# 2022-07-29_LVMi_Pressure_Sensor_-_1624.net
KiCad netlist of a schematic drawn in EAGLE
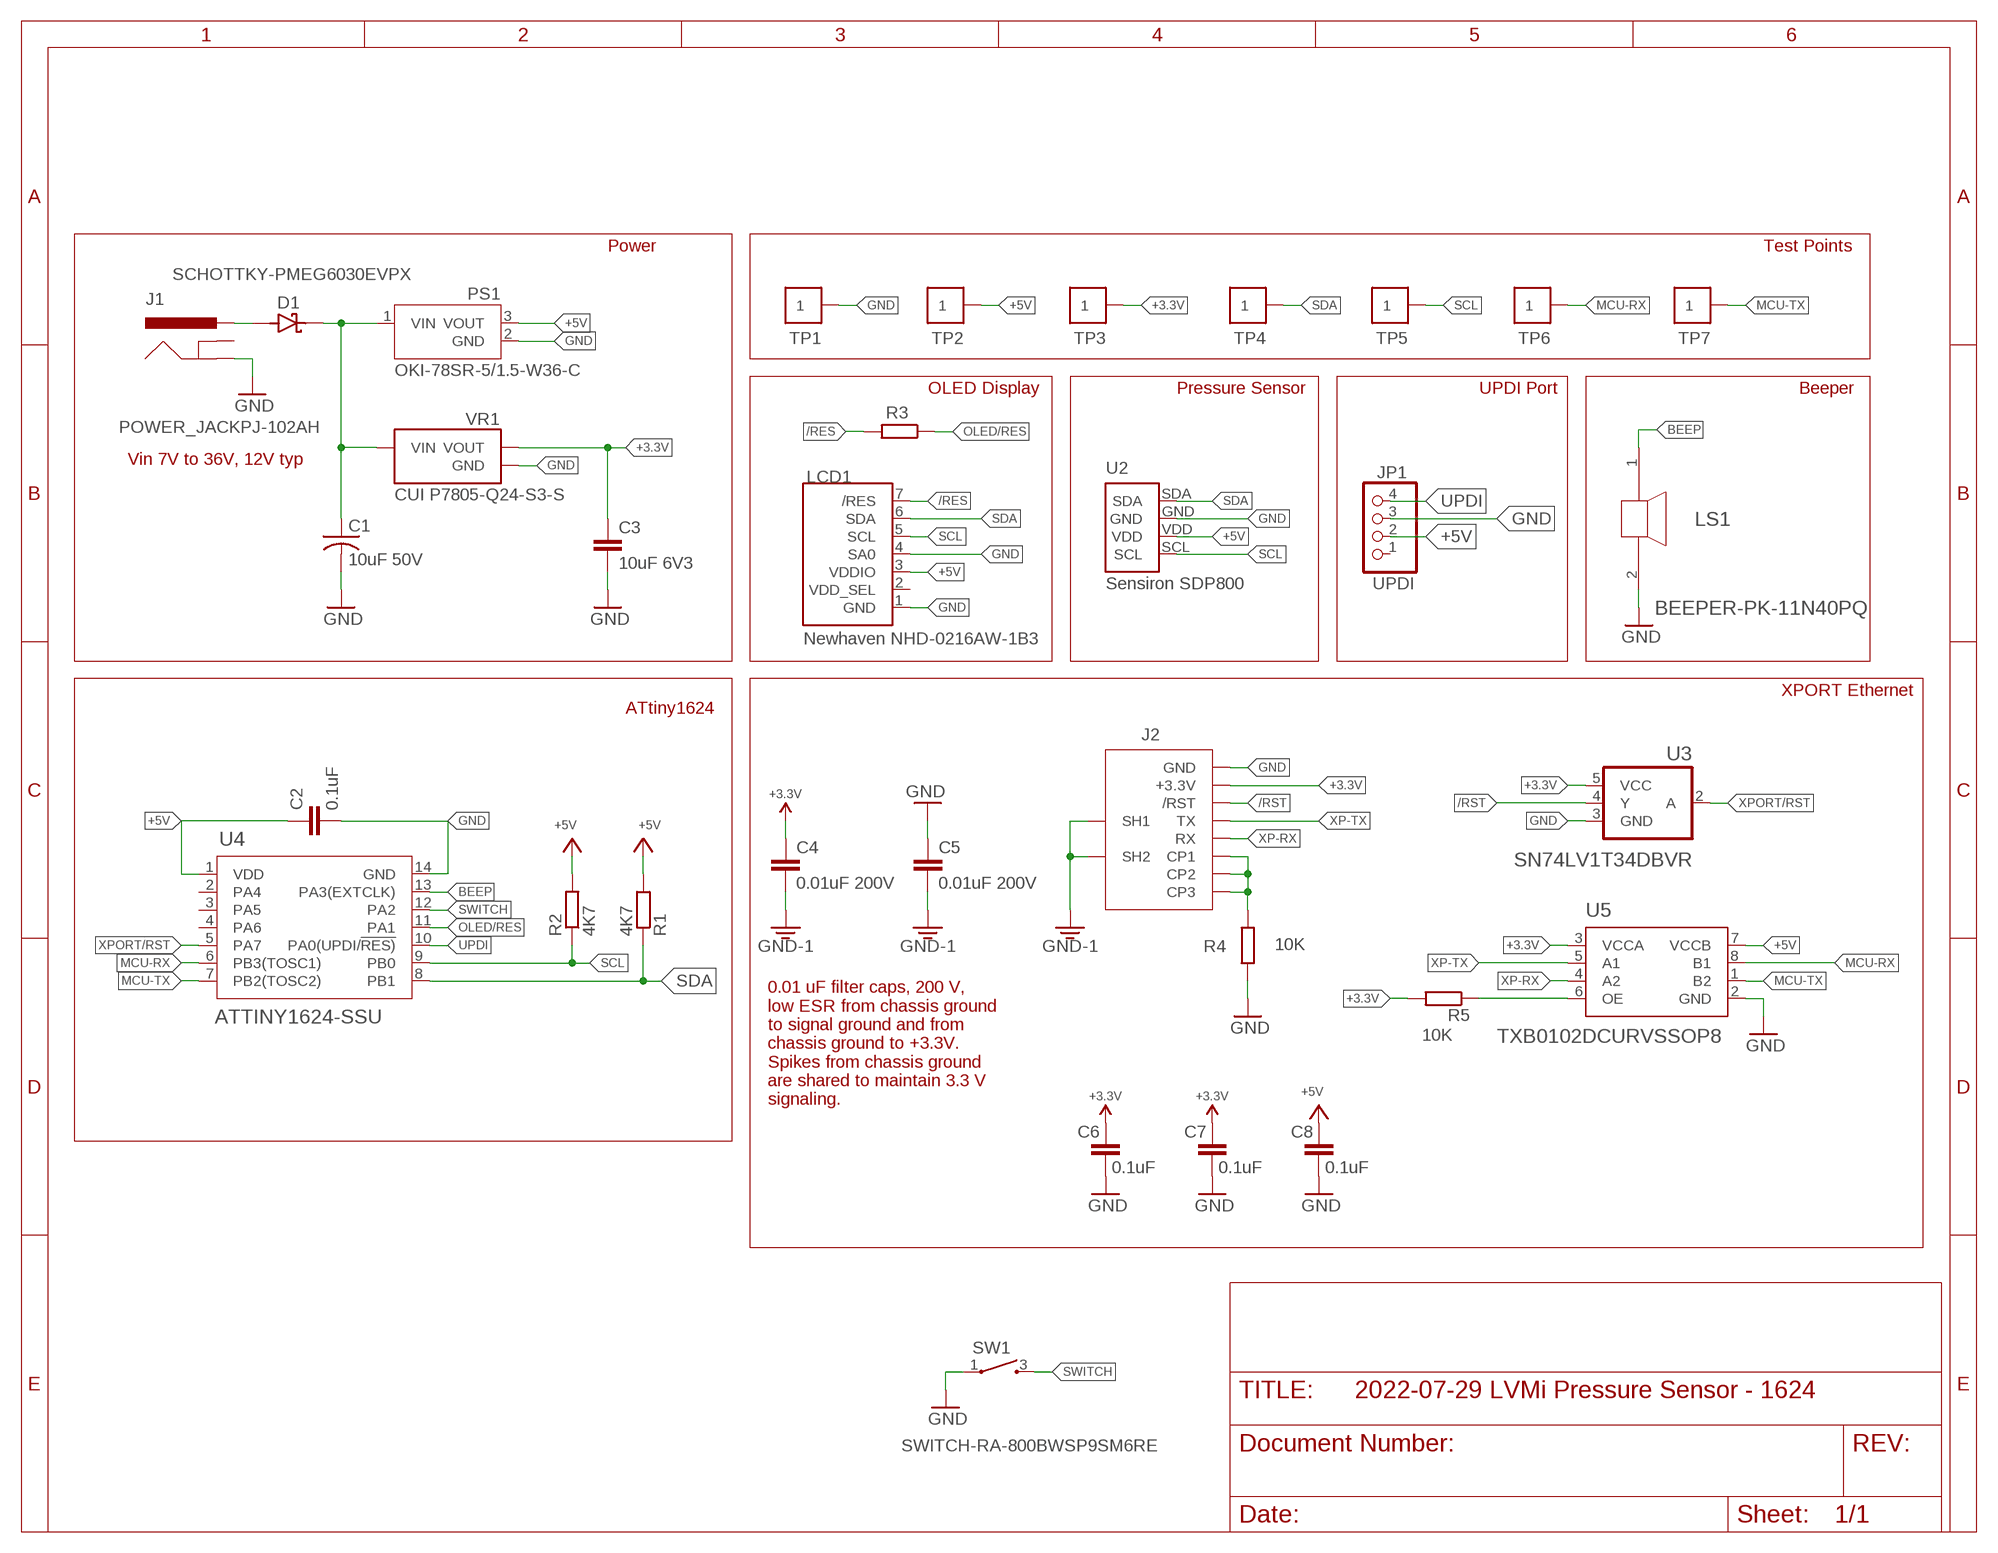
[diagram p0: schematic, sheet 1]

(export (version "E")
  (design (tool "Eeschema 10.0.6"))
  (components
    (comp (ref "C1")
      (value "10uF 50V")
      (footprint "eagle-import:C1210")
      (libsource (lib "eagle-import") (part "C-USC1210"))
    )
    (comp (ref "C2")
      (value "0.1uF")
      (footprint "eagle-import:C0805")
      (libsource (lib "eagle-import") (part "C-EUC0805"))
    )
    (comp (ref "C3")
      (value "10uF 6V3")
      (footprint "eagle-import:C0805")
      (libsource (lib "eagle-import") (part "C-EUC0805"))
    )
    (comp (ref "C4")
      (value "0.01uF 200V")
      (footprint "eagle-import:C0805")
      (libsource (lib "eagle-import") (part "C-EUC0805"))
    )
    (comp (ref "C5")
      (value "0.01uF 200V")
      (footprint "eagle-import:C0805")
      (libsource (lib "eagle-import") (part "C-EUC0805"))
    )
    (comp (ref "C6")
      (value "0.1uF")
      (footprint "eagle-import:C0805")
      (libsource (lib "eagle-import") (part "C-EUC0805"))
    )
    (comp (ref "C7")
      (value "0.1uF")
      (footprint "eagle-import:C0805")
      (libsource (lib "eagle-import") (part "C-EUC0805"))
    )
    (comp (ref "C8")
      (value "0.1uF")
      (footprint "eagle-import:C0805")
      (libsource (lib "eagle-import") (part "C-EUC0805"))
    )
    (comp (ref "D1")
      (value "SCHOTTKY-PMEG6030EVPX")
      (footprint "eagle-import:DIO_PMEG6030EVPX")
      (fields
        (field (name "DIGI-KEY_PART_NUMBER") "1727-1349-1-ND")
        (field (name "MF") "Nexperia USA")
        (field (name "MP") "PMEG6030EVPX")
      )
      (libsource (lib "eagle-import") (part "SCHOTTKY-PMEG6030EVPX"))
    )
    (comp (ref "J1")
      (value "POWER_JACKPJ-102AH")
      (footprint "eagle-import:PJ-102AH")
      (libsource (lib "eagle-import") (part "POWER_JACKPJ-102AH"))
    )
    (comp (ref "J2")
      (value "XPORTXPORT-2")
      (footprint "eagle-import:XPORT-2")
      (libsource (lib "eagle-import") (part "XPORTXPORT-2"))
    )
    (comp (ref "JP1")
      (value "UPDI")
      (footprint "eagle-import:1X04_90")
      (libsource (lib "eagle-import") (part "PINHD-1X4/90"))
    )
    (comp (ref "LCD1")
      (value "Newhaven NHD-0216AW-1B3")
      (footprint "eagle-import:LCD-NEWHAVEN-16X2")
      (libsource (lib "eagle-import") (part "LCD-NEWHAVEN-16X2"))
    )
    (comp (ref "LS1")
      (value "BEEPER-PK-11N40PQ")
      (footprint "eagle-import:PK-11N40PQ_MAL")
      (fields
        (field (name "MANUFACTURER_PART_NUMBER") "PK-11N40PQ")
        (field (name "COPYRIGHT") "Copyright (C) 2022 Ultra Librarian. All rights reserved.")
      )
      (libsource (lib "eagle-import") (part "BEEPER-PK-11N40PQ"))
    )
    (comp (ref "PS1")
      (value "OKI-78SR-5/1.5-W36-C")
      (footprint "eagle-import:CONV_OKI-78SR-5_1.5-W36-C")
      (fields
        (field (name "DIGI-KEY_PART_NUMBER") "811-2196-5-ND")
        (field (name "MF") "Murata Power Solutions Inc.")
      )
      (libsource (lib "eagle-import") (part "OKI-78SR-5/1.5-W36-C"))
    )
    (comp (ref "R1")
      (value "4K7")
      (footprint "eagle-import:R0805")
      (libsource (lib "eagle-import") (part "R-EU_R0805"))
    )
    (comp (ref "R2")
      (value "4K7")
      (footprint "eagle-import:R0805")
      (libsource (lib "eagle-import") (part "R-EU_R0805"))
    )
    (comp (ref "R3")
      (value "R-EU_R0805")
      (footprint "eagle-import:R0805")
      (libsource (lib "eagle-import") (part "R-EU_R0805"))
    )
    (comp (ref "R4")
      (value "10K")
      (footprint "eagle-import:R0805")
      (libsource (lib "eagle-import") (part "R-EU_R0805"))
    )
    (comp (ref "R5")
      (value "10K")
      (footprint "eagle-import:R0805")
      (libsource (lib "eagle-import") (part "R-EU_R0805"))
    )
    (comp (ref "SW1")
      (value "SWITCH-RA-800BWSP9SM6RE")
      (footprint "eagle-import:SWITCH-RA-800BWSP9SM6RE")
      (libsource (lib "eagle-import") (part "SWITCH-RA-800BWSP9SM6RE"))
    )
    (comp (ref "TP1")
      (value "GND")
      (footprint "eagle-import:TP5000-TESTPOINT-BLK")
      (libsource (lib "eagle-import") (part "TP5000-TESTPOINT-BLK"))
    )
    (comp (ref "TP2")
      (value "+5V")
      (footprint "eagle-import:TP5000-TESTPOINT-RED")
      (libsource (lib "eagle-import") (part "TP5000-TESTPOINT-RED"))
    )
    (comp (ref "TP3")
      (value "+3.3V")
      (footprint "eagle-import:TP5000-TESTPOINT-PUR")
      (libsource (lib "eagle-import") (part "TP5000-TESTPOINT-PUR"))
    )
    (comp (ref "TP4")
      (value "SDA")
      (footprint "eagle-import:TP5000-TESTPOINT-YEL")
      (libsource (lib "eagle-import") (part "TP5000-TESTPOINT-YEL"))
    )
    (comp (ref "TP5")
      (value "SCL")
      (footprint "eagle-import:TP5000-TESTPOINT-WHI")
      (libsource (lib "eagle-import") (part "TP5000-TESTPOINT-WHI"))
    )
    (comp (ref "TP6")
      (value "MCU-RX")
      (footprint "eagle-import:TP5000-TESTPOINT-WHI")
      (libsource (lib "eagle-import") (part "TP5000-TESTPOINT-WHI"))
    )
    (comp (ref "TP7")
      (value "MCU-TX")
      (footprint "eagle-import:TP5000-TESTPOINT-WHI")
      (libsource (lib "eagle-import") (part "TP5000-TESTPOINT-WHI"))
    )
    (comp (ref "U2")
      (value "Sensiron SDP800")
      (footprint "eagle-import:SDP800_PRESSURE_SENSOR")
      (libsource (lib "eagle-import") (part "SDP800_PRESSURE_SENSOR"))
    )
    (comp (ref "U3")
      (value "SN74LV1T34DBVR")
      (footprint "eagle-import:SOT95P280X145-5N")
      (fields (field (name "DIGI-KEY_PART_NUMBER") "296-37176-1-ND") (field (name "MF") "Texas Instruments"))
      (libsource (lib "eagle-import") (part "SN74LV1T34DBVR"))
    )
    (comp (ref "U4")
      (value "ATTINY1624-SSU")
      (footprint "eagle-import:SOIC150-14_MCH-M")
      (fields (field (name "COPYRIGHT") "Copyright (C) 2022 Ultra Librarian. All rights reserved."))
      (libsource (lib "eagle-import") (part "ATTINY1624-SSUSOIC150-14_MCH-M"))
    )
    (comp (ref "U5")
      (value "TXB0102DCURVSSOP8")
      (footprint "eagle-import:GHI-IC_VSSOP8(TI)")
      (libsource (lib "eagle-import") (part "TXB0102DCURVSSOP8"))
    )
    (comp (ref "VR1")
      (value "CUI P7805-Q24-S3-S")
      (footprint "eagle-import:CONV_P7805-Q24-S3-S")
      (fields (field (name "MF") "CUI") (field (name "MP") "P7805-Q12-S1R5-S"))
      (libsource (lib "eagle-import") (part "P7805-Q24-S3-S"))
    )
  )
  (nets
    (net (code "1") (name "+3.3V") (class "Default")
      (node (ref "C3") (pin "1") (pinfunction "1_1") (pintype "passive"))
      (node (ref "C4") (pin "1") (pinfunction "1_1") (pintype "passive"))
      (node (ref "C6") (pin "2") (pinfunction "2_2") (pintype "passive"))
      (node (ref "C7") (pin "2") (pinfunction "2_2") (pintype "passive"))
      (node (ref "J2") (pin "3.3V") (pinfunction "+3.3V_3.3V") (pintype "power_in"))
      (node (ref "R5") (pin "2") (pinfunction "2_2") (pintype "passive"))
      (node (ref "TP3") (pin "P$1") (pinfunction "1_P$1") (pintype "bidirectional"))
      (node (ref "U3") (pin "5") (pinfunction "VCC_5") (pintype "power_in"))
      (node (ref "U5") (pin "3") (pinfunction "VCCA_3") (pintype "power_in"))
      (node (ref "VR1") (pin "VOUT") (pinfunction "VOUT_VOUT") (pintype "power_in"))
    )
    (net (code "2") (name "+5V") (class "Default")
      (node (ref "C2") (pin "1") (pinfunction "1_1") (pintype "passive"))
      (node (ref "C8") (pin "2") (pinfunction "2_2") (pintype "passive"))
      (node (ref "JP1") (pin "2") (pinfunction "2_2") (pintype "passive"))
      (node (ref "LCD1") (pin "3") (pinfunction "VDDIO_3") (pintype "bidirectional"))
      (node (ref "PS1") (pin "3") (pinfunction "VOUT_3") (pintype "power_in"))
      (node (ref "R1") (pin "2") (pinfunction "2_2") (pintype "passive"))
      (node (ref "R2") (pin "2") (pinfunction "2_2") (pintype "passive"))
      (node (ref "TP2") (pin "P$1") (pinfunction "1_P$1") (pintype "bidirectional"))
      (node (ref "U2") (pin "VDD") (pinfunction "VDD_VDD") (pintype "bidirectional"))
      (node (ref "U4") (pin "1") (pinfunction "VDD_1") (pintype "power_in"))
      (node (ref "U5") (pin "7") (pinfunction "VCCB_7") (pintype "power_in"))
    )
    (net (code "3") (name "BEEP") (class "Default")
      (node (ref "LS1") (pin "1") (pinfunction "1_1") (pintype "passive"))
      (node (ref "U4") (pin "13") (pinfunction "PA3(EXTCLK)_13") (pintype "bidirectional"))
    )
    (net (code "4") (name "GND") (class "Default")
      (node (ref "C1") (pin "2") (pinfunction "2_2") (pintype "passive"))
      (node (ref "C2") (pin "2") (pinfunction "2_2") (pintype "passive"))
      (node (ref "C3") (pin "2") (pinfunction "2_2") (pintype "passive"))
      (node (ref "C5") (pin "1") (pinfunction "1_1") (pintype "passive"))
      (node (ref "C6") (pin "1") (pinfunction "1_1") (pintype "passive"))
      (node (ref "C7") (pin "1") (pinfunction "1_1") (pintype "passive"))
      (node (ref "C8") (pin "1") (pinfunction "1_1") (pintype "passive"))
      (node (ref "J1") (pin "GND") (pinfunction "GND_GND") (pintype "bidirectional"))
      (node (ref "J2") (pin "GND") (pinfunction "GND_GND") (pintype "power_in"))
      (node (ref "JP1") (pin "3") (pinfunction "3_3") (pintype "passive"))
      (node (ref "LCD1") (pin "1") (pinfunction "GND_1") (pintype "bidirectional"))
      (node (ref "LCD1") (pin "4") (pinfunction "SA0_4") (pintype "bidirectional"))
      (node (ref "LS1") (pin "2") (pinfunction "2_2") (pintype "passive"))
      (node (ref "PS1") (pin "2") (pinfunction "GND_2") (pintype "power_in"))
      (node (ref "R4") (pin "2") (pinfunction "2_2") (pintype "passive"))
      (node (ref "SW1") (pin "1") (pinfunction "1_1") (pintype "passive"))
      (node (ref "TP1") (pin "P$1") (pinfunction "1_P$1") (pintype "bidirectional"))
      (node (ref "U2") (pin "GND") (pinfunction "GND_GND") (pintype "bidirectional"))
      (node (ref "U3") (pin "3") (pinfunction "GND_3") (pintype "power_in"))
      (node (ref "U4") (pin "14") (pinfunction "GND_14") (pintype "passive"))
      (node (ref "U5") (pin "2") (pinfunction "GND_2") (pintype "power_in"))
      (node (ref "VR1") (pin "GND") (pinfunction "GND_GND") (pintype "power_in"))
    )
    (net (code "5") (name "GND-1") (class "Default")
      (node (ref "C4") (pin "2") (pinfunction "2_2") (pintype "passive"))
      (node (ref "C5") (pin "2") (pinfunction "2_2") (pintype "passive"))
      (node (ref "J2") (pin "P$1") (pinfunction "SH1_P$1") (pintype "bidirectional"))
      (node (ref "J2") (pin "P$2") (pinfunction "SH2_P$2") (pintype "bidirectional"))
    )
    (net (code "6") (name "MCU-RX") (class "Default")
      (node (ref "TP6") (pin "P$1") (pinfunction "1_P$1") (pintype "bidirectional"))
      (node (ref "U4") (pin "6") (pinfunction "PB3(TOSC1)_6") (pintype "bidirectional"))
      (node (ref "U5") (pin "8") (pinfunction "B1_8") (pintype "bidirectional"))
    )
    (net (code "7") (name "MCU-TX") (class "Default")
      (node (ref "TP7") (pin "P$1") (pinfunction "1_P$1") (pintype "bidirectional"))
      (node (ref "U4") (pin "7") (pinfunction "PB2(TOSC2)_7") (pintype "bidirectional"))
      (node (ref "U5") (pin "1") (pinfunction "B2_1") (pintype "bidirectional"))
    )
    (net (code "8") (name "Net-(D1-A)") (class "Default")
      (node (ref "D1") (pin "2") (pinfunction "A_2") (pintype "passive"))
      (node (ref "J1") (pin "PWR") (pinfunction "PWR_PWR") (pintype "bidirectional"))
    )
    (net (code "9") (name "Net-(D1-K)") (class "Default")
      (node (ref "C1") (pin "1") (pinfunction "1_1") (pintype "passive"))
      (node (ref "D1") (pin "1") (pinfunction "K_1") (pintype "passive"))
      (node (ref "PS1") (pin "1") (pinfunction "VIN_1") (pintype "input"))
      (node (ref "VR1") (pin "VIN") (pinfunction "VIN_VIN") (pintype "power_in"))
    )
    (net (code "10") (name "Net-(J2-PadCP1)") (class "Default")
      (node (ref "J2") (pin "CP1") (pinfunction "CP1_CP1") (pintype "bidirectional"))
      (node (ref "J2") (pin "CP2") (pinfunction "CP2_CP2") (pintype "bidirectional"))
      (node (ref "J2") (pin "CP3") (pinfunction "CP3_CP3") (pintype "bidirectional"))
      (node (ref "R4") (pin "1") (pinfunction "1_1") (pintype "passive"))
    )
    (net (code "11") (name "Net-(U5-OE)") (class "Default")
      (node (ref "R5") (pin "1") (pinfunction "1_1") (pintype "passive"))
      (node (ref "U5") (pin "6") (pinfunction "OE_6") (pintype "input"))
    )
    (net (code "12") (name "OLED{slash}RES") (class "Default")
      (node (ref "R3") (pin "1") (pinfunction "1_1") (pintype "passive"))
      (node (ref "U4") (pin "11") (pinfunction "PA1_11") (pintype "bidirectional"))
    )
    (net (code "13") (name "SCL") (class "Default")
      (node (ref "LCD1") (pin "5") (pinfunction "SCL_5") (pintype "bidirectional"))
      (node (ref "R2") (pin "1") (pinfunction "1_1") (pintype "passive"))
      (node (ref "TP5") (pin "P$1") (pinfunction "1_P$1") (pintype "bidirectional"))
      (node (ref "U2") (pin "SCL") (pinfunction "SCL_SCL") (pintype "bidirectional"))
      (node (ref "U4") (pin "9") (pinfunction "PB0_9") (pintype "bidirectional"))
    )
    (net (code "14") (name "SDA") (class "Default")
      (node (ref "LCD1") (pin "6") (pinfunction "SDA_6") (pintype "bidirectional"))
      (node (ref "R1") (pin "1") (pinfunction "1_1") (pintype "passive"))
      (node (ref "TP4") (pin "P$1") (pinfunction "1_P$1") (pintype "bidirectional"))
      (node (ref "U2") (pin "SDA") (pinfunction "SDA_SDA") (pintype "bidirectional"))
      (node (ref "U4") (pin "8") (pinfunction "PB1_8") (pintype "bidirectional"))
    )
    (net (code "15") (name "SWITCH") (class "Default")
      (node (ref "SW1") (pin "3") (pinfunction "2_3") (pintype "passive"))
      (node (ref "U4") (pin "12") (pinfunction "PA2_12") (pintype "bidirectional"))
    )
    (net (code "16") (name "UPDI") (class "Default")
      (node (ref "JP1") (pin "4") (pinfunction "4_4") (pintype "passive"))
      (node (ref "U4") (pin "10") (pinfunction "PA0(UPDI/~{RES})_10") (pintype "bidirectional"))
    )
    (net (code "17") (name "XP-RX") (class "Default")
      (node (ref "J2") (pin "RX") (pinfunction "RX_RX") (pintype "input"))
      (node (ref "U5") (pin "4") (pinfunction "A2_4") (pintype "bidirectional"))
    )
    (net (code "18") (name "XP-TX") (class "Default")
      (node (ref "J2") (pin "TX") (pinfunction "TX_TX") (pintype "output"))
      (node (ref "U5") (pin "5") (pinfunction "A1_5") (pintype "bidirectional"))
    )
    (net (code "19") (name "XPORT{slash}RST") (class "Default")
      (node (ref "U3") (pin "2") (pinfunction "A_2") (pintype "input"))
      (node (ref "U4") (pin "5") (pinfunction "PA7_5") (pintype "bidirectional"))
    )
    (net (code "20") (name "unconnected-(J1-GNDBREAK-PadGNDBRK)") (class "Default")
      (node (ref "J1") (pin "GNDBRK") (pinfunction "GNDBREAK_GNDBRK") (pintype "bidirectional"))
    )
    (net (code "21") (name "unconnected-(JP1-Pad1)") (class "Default")
      (node (ref "JP1") (pin "1") (pinfunction "1_1") (pintype "passive"))
    )
    (net (code "22") (name "unconnected-(LCD1-VDD_SEL-Pad2)") (class "Default")
      (node (ref "LCD1") (pin "2") (pinfunction "VDD_SEL_2") (pintype "bidirectional"))
    )
    (net (code "23") (name "unconnected-(U4-PA4-Pad2)") (class "Default")
      (node (ref "U4") (pin "2") (pinfunction "PA4_2") (pintype "bidirectional"))
    )
    (net (code "24") (name "unconnected-(U4-PA5-Pad3)") (class "Default")
      (node (ref "U4") (pin "3") (pinfunction "PA5_3") (pintype "bidirectional"))
    )
    (net (code "25") (name "unconnected-(U4-PA6-Pad4)") (class "Default")
      (node (ref "U4") (pin "4") (pinfunction "PA6_4") (pintype "bidirectional"))
    )
    (net (code "26") (name "{slash}RES") (class "Default")
      (node (ref "LCD1") (pin "7") (pinfunction "/RES_7") (pintype "bidirectional"))
      (node (ref "R3") (pin "2") (pinfunction "2_2") (pintype "passive"))
    )
    (net (code "27") (name "{slash}RST") (class "Default")
      (node (ref "J2") (pin "/RST") (pinfunction "/RST_/RST") (pintype "input"))
      (node (ref "U3") (pin "4") (pinfunction "Y_4") (pintype "output"))
    )
  )
)
